# DM_V1_FPGA.net
KiCad netlist of a schematic drawn in Altium Designer
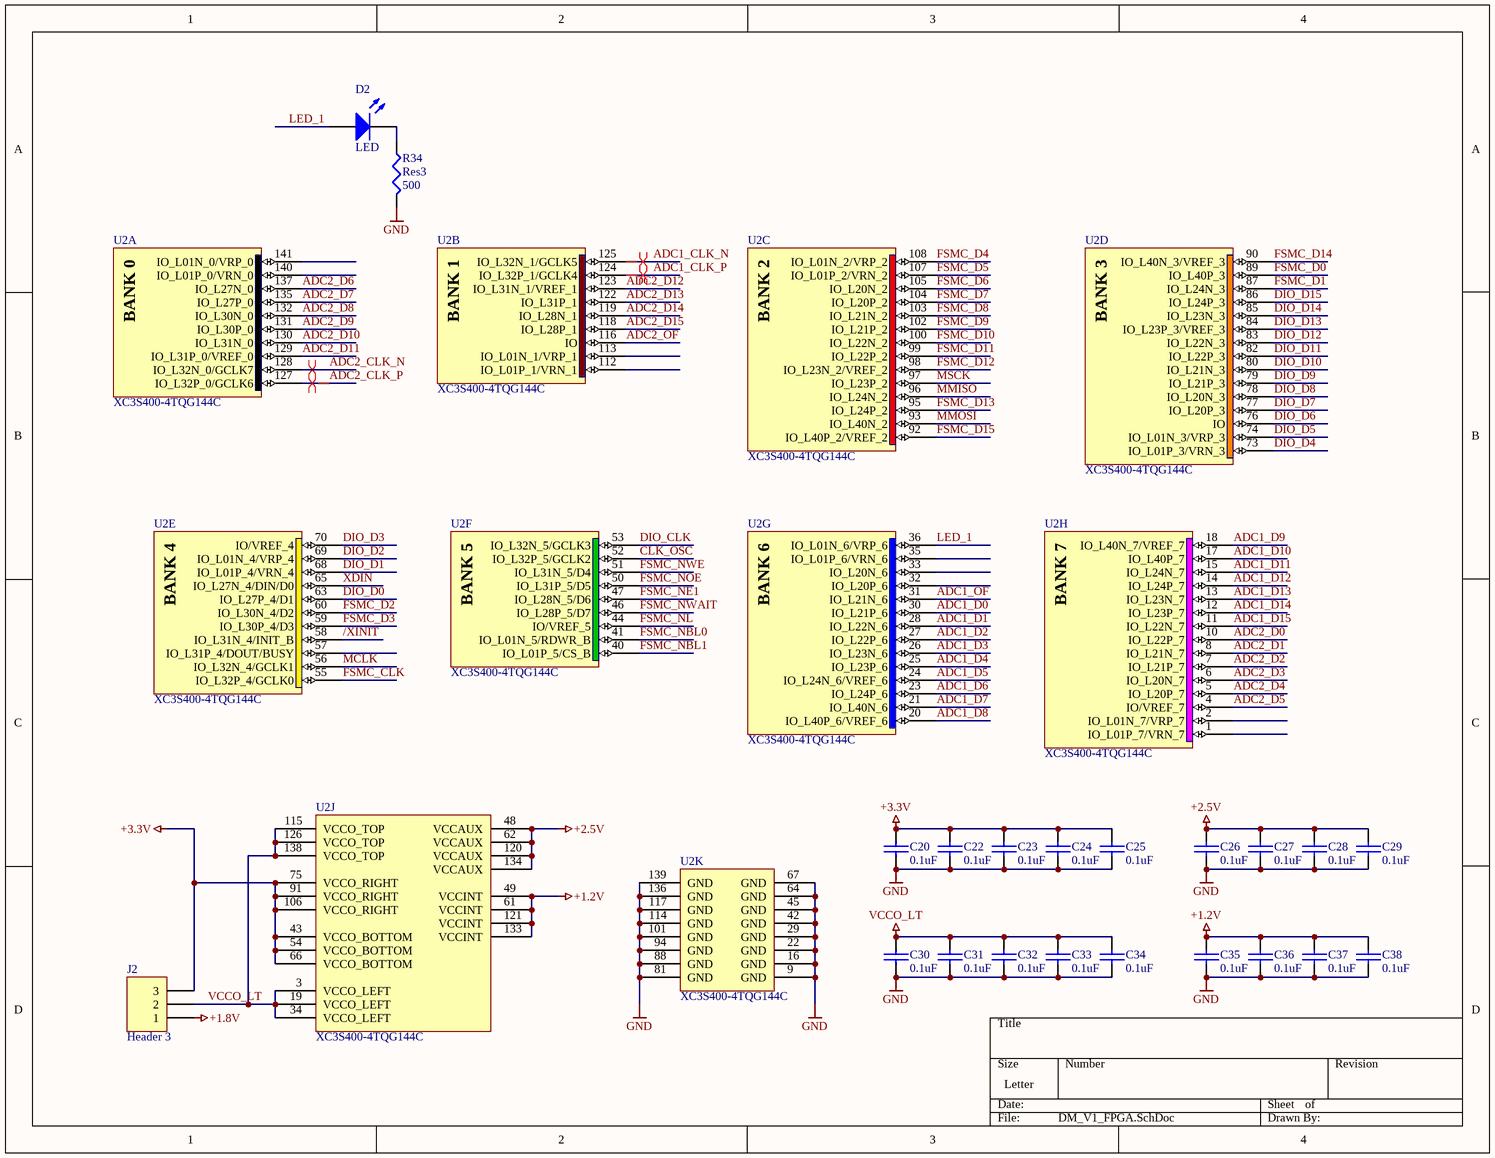
[diagram p0: DM_V1_FPGA.SchDoc]

(export (version "E")
  (design (tool "Eeschema 10.0.6"))
  (components
    (comp (ref "C20")
      (value "0.1uF")
      (footprint "1608[0603]")
      (description "Ceramic Chip-capacitor 0603")
      (fields (field (name "VOLTAGE") "25") (field (name "Comment") "0.1"))
      (libsource (lib "ISCapacitor") (part "CC0603-0.1MKF X7R"))
    )
    (comp (ref "C22")
      (value "0.1uF")
      (footprint "1608[0603]")
      (description "Ceramic Chip-capacitor 0603")
      (fields (field (name "VOLTAGE") "25") (field (name "Comment") "0.1"))
      (libsource (lib "ISCapacitor") (part "CC0603-0.1MKF X7R"))
    )
    (comp (ref "C23")
      (value "0.1uF")
      (footprint "1608[0603]")
      (description "Ceramic Chip-capacitor 0603")
      (fields (field (name "VOLTAGE") "25") (field (name "Comment") "0.1"))
      (libsource (lib "ISCapacitor") (part "CC0603-0.1MKF X7R"))
    )
    (comp (ref "C24")
      (value "0.1uF")
      (footprint "1608[0603]")
      (description "Ceramic Chip-capacitor 0603")
      (fields (field (name "VOLTAGE") "25") (field (name "Comment") "0.1"))
      (libsource (lib "ISCapacitor") (part "CC0603-0.1MKF X7R"))
    )
    (comp (ref "C25")
      (value "0.1uF")
      (footprint "1608[0603]")
      (description "Ceramic Chip-capacitor 0603")
      (fields (field (name "VOLTAGE") "25") (field (name "Comment") "0.1"))
      (libsource (lib "ISCapacitor") (part "CC0603-0.1MKF X7R"))
    )
    (comp (ref "C26")
      (value "0.1uF")
      (footprint "1608[0603]")
      (description "Ceramic Chip-capacitor 0603")
      (fields (field (name "VOLTAGE") "25") (field (name "Comment") "0.1"))
      (libsource (lib "ISCapacitor") (part "CC0603-0.1MKF X7R"))
    )
    (comp (ref "C27")
      (value "0.1uF")
      (footprint "1608[0603]")
      (description "Ceramic Chip-capacitor 0603")
      (fields (field (name "VOLTAGE") "25") (field (name "Comment") "0.1"))
      (libsource (lib "ISCapacitor") (part "CC0603-0.1MKF X7R"))
    )
    (comp (ref "C28")
      (value "0.1uF")
      (footprint "1608[0603]")
      (description "Ceramic Chip-capacitor 0603")
      (fields (field (name "VOLTAGE") "25") (field (name "Comment") "0.1"))
      (libsource (lib "ISCapacitor") (part "CC0603-0.1MKF X7R"))
    )
    (comp (ref "C29")
      (value "0.1uF")
      (footprint "1608[0603]")
      (description "Ceramic Chip-capacitor 0603")
      (fields (field (name "VOLTAGE") "25") (field (name "Comment") "0.1"))
      (libsource (lib "ISCapacitor") (part "CC0603-0.1MKF X7R"))
    )
    (comp (ref "C30")
      (value "0.1uF")
      (footprint "1608[0603]")
      (description "Ceramic Chip-capacitor 0603")
      (fields (field (name "VOLTAGE") "25") (field (name "Comment") "0.1"))
      (libsource (lib "ISCapacitor") (part "CC0603-0.1MKF X7R"))
    )
    (comp (ref "C31")
      (value "0.1uF")
      (footprint "1608[0603]")
      (description "Ceramic Chip-capacitor 0603")
      (fields (field (name "VOLTAGE") "25") (field (name "Comment") "0.1"))
      (libsource (lib "ISCapacitor") (part "CC0603-0.1MKF X7R"))
    )
    (comp (ref "C32")
      (value "0.1uF")
      (footprint "1608[0603]")
      (description "Ceramic Chip-capacitor 0603")
      (fields (field (name "VOLTAGE") "25") (field (name "Comment") "0.1"))
      (libsource (lib "ISCapacitor") (part "CC0603-0.1MKF X7R"))
    )
    (comp (ref "C33")
      (value "0.1uF")
      (footprint "1608[0603]")
      (description "Ceramic Chip-capacitor 0603")
      (fields (field (name "VOLTAGE") "25") (field (name "Comment") "0.1"))
      (libsource (lib "ISCapacitor") (part "CC0603-0.1MKF X7R"))
    )
    (comp (ref "C34")
      (value "0.1uF")
      (footprint "1608[0603]")
      (description "Ceramic Chip-capacitor 0603")
      (fields (field (name "VOLTAGE") "25") (field (name "Comment") "0.1"))
      (libsource (lib "ISCapacitor") (part "CC0603-0.1MKF X7R"))
    )
    (comp (ref "C35")
      (value "0.1uF")
      (footprint "1608[0603]")
      (description "Ceramic Chip-capacitor 0603")
      (fields (field (name "VOLTAGE") "25") (field (name "Comment") "0.1"))
      (libsource (lib "ISCapacitor") (part "CC0603-0.1MKF X7R"))
    )
    (comp (ref "C36")
      (value "0.1uF")
      (footprint "1608[0603]")
      (description "Ceramic Chip-capacitor 0603")
      (fields (field (name "VOLTAGE") "25") (field (name "Comment") "0.1"))
      (libsource (lib "ISCapacitor") (part "CC0603-0.1MKF X7R"))
    )
    (comp (ref "C37")
      (value "0.1uF")
      (footprint "1608[0603]")
      (description "Ceramic Chip-capacitor 0603")
      (fields (field (name "VOLTAGE") "25") (field (name "Comment") "0.1"))
      (libsource (lib "ISCapacitor") (part "CC0603-0.1MKF X7R"))
    )
    (comp (ref "C38")
      (value "0.1uF")
      (footprint "1608[0603]")
      (description "Ceramic Chip-capacitor 0603")
      (fields (field (name "VOLTAGE") "25") (field (name "Comment") "0.1"))
      (libsource (lib "ISCapacitor") (part "CC0603-0.1MKF X7R"))
    )
    (comp (ref "D2")
      (value "LED")
      (footprint "1608[0603]")
      (description "Typical RED, GREEN, YELLOW, AMBER GaAs LED")
      (fields (field (name "PUBLISHER") "Altium Limited"))
      (libsource (lib "Miscellaneous Devices") (part "LED2"))
    )
    (comp (ref "J2")
      (value "Header 3")
      (footprint "HDR1X3")
      (description "Header, 3-Pin")
      (fields (field (name "PUBLISHER") "Altium Limited"))
      (libsource (lib "Miscellaneous Connectors") (part "Header 3"))
    )
    (comp (ref "R34")
      (value "Res3")
      (footprint "J1-0603")
      (description "Resistor")
      (fields (field (name "ALTIUM_VALUE") "500") (field (name "PUBLISHER") "Altium Limited"))
      (libsource (lib "Miscellaneous Devices") (part "Res3"))
    )
    (comp (ref "U2")
      (value "XC3S400-4TQG144C")
      (footprint "TQG144_N")
      (description "Spartan-3 1.2V FPGA, 97 User I/Os, 144-Pin TQFP, Standard Performance, Commercial Grade, Pb-Free")
      (fields (field (name "PUBLISHER") "Altium Limited"))
      (libsource (lib "Xilinx Spartan-3") (part "XC3S400-4TQG144C"))
    )
  )
  (nets
    (net (code "1") (name "+1.2V") (class "Default")
      (node (ref "C35") (pin "2") (pintype "passive"))
      (node (ref "C36") (pin "2") (pintype "passive"))
      (node (ref "C37") (pin "2") (pintype "passive"))
      (node (ref "C38") (pin "2") (pintype "passive"))
      (node (ref "U2") (pin "121") (pinfunction "VCCINT_121") (pintype "power_in"))
      (node (ref "U2") (pin "133") (pinfunction "VCCINT_133") (pintype "power_in"))
      (node (ref "U2") (pin "49") (pinfunction "VCCINT_49") (pintype "power_in"))
      (node (ref "U2") (pin "61") (pinfunction "VCCINT_61") (pintype "power_in"))
    )
    (net (code "2") (name "+1.8V") (class "Default")
      (node (ref "J2") (pin "1") (pinfunction "1_1") (pintype "passive"))
    )
    (net (code "3") (name "+2.5V") (class "Default")
      (node (ref "C26") (pin "2") (pintype "passive"))
      (node (ref "C27") (pin "2") (pintype "passive"))
      (node (ref "C28") (pin "2") (pintype "passive"))
      (node (ref "C29") (pin "2") (pintype "passive"))
      (node (ref "U2") (pin "120") (pinfunction "VCCAUX_120") (pintype "power_in"))
      (node (ref "U2") (pin "134") (pinfunction "VCCAUX_134") (pintype "power_in"))
      (node (ref "U2") (pin "48") (pinfunction "VCCAUX_48") (pintype "power_in"))
      (node (ref "U2") (pin "62") (pinfunction "VCCAUX_62") (pintype "power_in"))
    )
    (net (code "4") (name "+3.3V") (class "Default")
      (node (ref "C20") (pin "2") (pintype "passive"))
      (node (ref "C22") (pin "2") (pintype "passive"))
      (node (ref "C23") (pin "2") (pintype "passive"))
      (node (ref "C24") (pin "2") (pintype "passive"))
      (node (ref "C25") (pin "2") (pintype "passive"))
      (node (ref "J2") (pin "3") (pinfunction "3_3") (pintype "passive"))
      (node (ref "U2") (pin "106") (pinfunction "VCCO_RIGHT_106") (pintype "power_in"))
      (node (ref "U2") (pin "43") (pinfunction "VCCO_BOTTOM_43") (pintype "power_in"))
      (node (ref "U2") (pin "54") (pinfunction "VCCO_BOTTOM_54") (pintype "power_in"))
      (node (ref "U2") (pin "66") (pinfunction "VCCO_BOTTOM_66") (pintype "power_in"))
      (node (ref "U2") (pin "75") (pinfunction "VCCO_RIGHT_75") (pintype "power_in"))
      (node (ref "U2") (pin "91") (pinfunction "VCCO_RIGHT_91") (pintype "power_in"))
    )
    (net (code "5") (name "/ADC1_CLK_N") (class "Default")
      (node (ref "U2") (pin "125") (pinfunction "IO_L32N_1/GCLK5_125") (pintype "bidirectional"))
    )
    (net (code "6") (name "/ADC1_CLK_P") (class "Default")
      (node (ref "U2") (pin "124") (pinfunction "IO_L32P_1/GCLK4_124") (pintype "bidirectional"))
    )
    (net (code "7") (name "/ADC1_D0") (class "Default")
      (node (ref "U2") (pin "30") (pinfunction "IO_L21P_6_30") (pintype "bidirectional"))
    )
    (net (code "8") (name "/ADC1_D1") (class "Default")
      (node (ref "U2") (pin "28") (pinfunction "IO_L22N_6_28") (pintype "bidirectional"))
    )
    (net (code "9") (name "/ADC1_D2") (class "Default")
      (node (ref "U2") (pin "27") (pinfunction "IO_L22P_6_27") (pintype "bidirectional"))
    )
    (net (code "10") (name "/ADC1_D3") (class "Default")
      (node (ref "U2") (pin "26") (pinfunction "IO_L23N_6_26") (pintype "bidirectional"))
    )
    (net (code "11") (name "/ADC1_D4") (class "Default")
      (node (ref "U2") (pin "25") (pinfunction "IO_L23P_6_25") (pintype "bidirectional"))
    )
    (net (code "12") (name "/ADC1_D5") (class "Default")
      (node (ref "U2") (pin "24") (pinfunction "IO_L24N_6/VREF_6_24") (pintype "bidirectional"))
    )
    (net (code "13") (name "/ADC1_D6") (class "Default")
      (node (ref "U2") (pin "23") (pinfunction "IO_L24P_6_23") (pintype "bidirectional"))
    )
    (net (code "14") (name "/ADC1_D7") (class "Default")
      (node (ref "U2") (pin "21") (pinfunction "IO_L40N_6_21") (pintype "bidirectional"))
    )
    (net (code "15") (name "/ADC1_D8") (class "Default")
      (node (ref "U2") (pin "20") (pinfunction "IO_L40P_6/VREF_6_20") (pintype "bidirectional"))
    )
    (net (code "16") (name "/ADC1_D9") (class "Default")
      (node (ref "U2") (pin "18") (pinfunction "IO_L40N_7/VREF_7_18") (pintype "bidirectional"))
    )
    (net (code "17") (name "/ADC1_D10") (class "Default")
      (node (ref "U2") (pin "17") (pinfunction "IO_L40P_7_17") (pintype "bidirectional"))
    )
    (net (code "18") (name "/ADC1_D11") (class "Default")
      (node (ref "U2") (pin "15") (pinfunction "IO_L24N_7_15") (pintype "bidirectional"))
    )
    (net (code "19") (name "/ADC1_D12") (class "Default")
      (node (ref "U2") (pin "14") (pinfunction "IO_L24P_7_14") (pintype "bidirectional"))
    )
    (net (code "20") (name "/ADC1_D13") (class "Default")
      (node (ref "U2") (pin "13") (pinfunction "IO_L23N_7_13") (pintype "bidirectional"))
    )
    (net (code "21") (name "/ADC1_D14") (class "Default")
      (node (ref "U2") (pin "12") (pinfunction "IO_L23P_7_12") (pintype "bidirectional"))
    )
    (net (code "22") (name "/ADC1_D15") (class "Default")
      (node (ref "U2") (pin "11") (pinfunction "IO_L22N_7_11") (pintype "bidirectional"))
    )
    (net (code "23") (name "/ADC1_OF") (class "Default")
      (node (ref "U2") (pin "31") (pinfunction "IO_L21N_6_31") (pintype "bidirectional"))
    )
    (net (code "24") (name "/ADC2_CLK_N") (class "Default")
      (node (ref "U2") (pin "128") (pinfunction "IO_L32N_0/GCLK7_128") (pintype "bidirectional"))
    )
    (net (code "25") (name "/ADC2_CLK_P") (class "Default")
      (node (ref "U2") (pin "127") (pinfunction "IO_L32P_0/GCLK6_127") (pintype "bidirectional"))
    )
    (net (code "26") (name "/ADC2_D0") (class "Default")
      (node (ref "U2") (pin "10") (pinfunction "IO_L22P_7_10") (pintype "bidirectional"))
    )
    (net (code "27") (name "/ADC2_D1") (class "Default")
      (node (ref "U2") (pin "8") (pinfunction "IO_L21N_7_8") (pintype "bidirectional"))
    )
    (net (code "28") (name "/ADC2_D2") (class "Default")
      (node (ref "U2") (pin "7") (pinfunction "IO_L21P_7_7") (pintype "bidirectional"))
    )
    (net (code "29") (name "/ADC2_D3") (class "Default")
      (node (ref "U2") (pin "6") (pinfunction "IO_L20N_7_6") (pintype "bidirectional"))
    )
    (net (code "30") (name "/ADC2_D4") (class "Default")
      (node (ref "U2") (pin "5") (pinfunction "IO_L20P_7_5") (pintype "bidirectional"))
    )
    (net (code "31") (name "/ADC2_D5") (class "Default")
      (node (ref "U2") (pin "4") (pinfunction "IO/VREF_7_4") (pintype "bidirectional"))
    )
    (net (code "32") (name "/ADC2_D6") (class "Default")
      (node (ref "U2") (pin "137") (pinfunction "IO_L27N_0_137") (pintype "bidirectional"))
    )
    (net (code "33") (name "/ADC2_D7") (class "Default")
      (node (ref "U2") (pin "135") (pinfunction "IO_L27P_0_135") (pintype "bidirectional"))
    )
    (net (code "34") (name "/ADC2_D8") (class "Default")
      (node (ref "U2") (pin "132") (pinfunction "IO_L30N_0_132") (pintype "bidirectional"))
    )
    (net (code "35") (name "/ADC2_D9") (class "Default")
      (node (ref "U2") (pin "131") (pinfunction "IO_L30P_0_131") (pintype "bidirectional"))
    )
    (net (code "36") (name "/ADC2_D10") (class "Default")
      (node (ref "U2") (pin "130") (pinfunction "IO_L31N_0_130") (pintype "bidirectional"))
    )
    (net (code "37") (name "/ADC2_D11") (class "Default")
      (node (ref "U2") (pin "129") (pinfunction "IO_L31P_0/VREF_0_129") (pintype "bidirectional"))
    )
    (net (code "38") (name "/ADC2_D12") (class "Default")
      (node (ref "U2") (pin "123") (pinfunction "IO_L31N_1/VREF_1_123") (pintype "bidirectional"))
    )
    (net (code "39") (name "/ADC2_D13") (class "Default")
      (node (ref "U2") (pin "122") (pinfunction "IO_L31P_1_122") (pintype "bidirectional"))
    )
    (net (code "40") (name "/ADC2_D14") (class "Default")
      (node (ref "U2") (pin "119") (pinfunction "IO_L28N_1_119") (pintype "bidirectional"))
    )
    (net (code "41") (name "/ADC2_D15") (class "Default")
      (node (ref "U2") (pin "118") (pinfunction "IO_L28P_1_118") (pintype "bidirectional"))
    )
    (net (code "42") (name "/ADC2_OF") (class "Default")
      (node (ref "U2") (pin "116") (pinfunction "IO_116") (pintype "bidirectional"))
    )
    (net (code "43") (name "/CLK_OSC") (class "Default")
      (node (ref "U2") (pin "52") (pinfunction "IO_L32P_5/GCLK2_52") (pintype "bidirectional"))
    )
    (net (code "44") (name "/DIO_CLK") (class "Default")
      (node (ref "U2") (pin "53") (pinfunction "IO_L32N_5/GCLK3_53") (pintype "bidirectional"))
    )
    (net (code "45") (name "/DIO_D0") (class "Default")
      (node (ref "U2") (pin "63") (pinfunction "IO_L27P_4/D1_63") (pintype "bidirectional"))
    )
    (net (code "46") (name "/DIO_D1") (class "Default")
      (node (ref "U2") (pin "68") (pinfunction "IO_L01P_4/VRN_4_68") (pintype "bidirectional"))
    )
    (net (code "47") (name "/DIO_D2") (class "Default")
      (node (ref "U2") (pin "69") (pinfunction "IO_L01N_4/VRP_4_69") (pintype "bidirectional"))
    )
    (net (code "48") (name "/DIO_D3") (class "Default")
      (node (ref "U2") (pin "70") (pinfunction "IO/VREF_4_70") (pintype "bidirectional"))
    )
    (net (code "49") (name "/DIO_D4") (class "Default")
      (node (ref "U2") (pin "73") (pinfunction "IO_L01P_3/VRN_3_73") (pintype "bidirectional"))
    )
    (net (code "50") (name "/DIO_D5") (class "Default")
      (node (ref "U2") (pin "74") (pinfunction "IO_L01N_3/VRP_3_74") (pintype "bidirectional"))
    )
    (net (code "51") (name "/DIO_D6") (class "Default")
      (node (ref "U2") (pin "76") (pinfunction "IO_76") (pintype "bidirectional"))
    )
    (net (code "52") (name "/DIO_D7") (class "Default")
      (node (ref "U2") (pin "77") (pinfunction "IO_L20P_3_77") (pintype "bidirectional"))
    )
    (net (code "53") (name "/DIO_D8") (class "Default")
      (node (ref "U2") (pin "78") (pinfunction "IO_L20N_3_78") (pintype "bidirectional"))
    )
    (net (code "54") (name "/DIO_D9") (class "Default")
      (node (ref "U2") (pin "79") (pinfunction "IO_L21P_3_79") (pintype "bidirectional"))
    )
    (net (code "55") (name "/DIO_D10") (class "Default")
      (node (ref "U2") (pin "80") (pinfunction "IO_L21N_3_80") (pintype "bidirectional"))
    )
    (net (code "56") (name "/DIO_D11") (class "Default")
      (node (ref "U2") (pin "82") (pinfunction "IO_L22P_3_82") (pintype "bidirectional"))
    )
    (net (code "57") (name "/DIO_D12") (class "Default")
      (node (ref "U2") (pin "83") (pinfunction "IO_L22N_3_83") (pintype "bidirectional"))
    )
    (net (code "58") (name "/DIO_D13") (class "Default")
      (node (ref "U2") (pin "84") (pinfunction "IO_L23P_3/VREF_3_84") (pintype "bidirectional"))
    )
    (net (code "59") (name "/DIO_D14") (class "Default")
      (node (ref "U2") (pin "85") (pinfunction "IO_L23N_3_85") (pintype "bidirectional"))
    )
    (net (code "60") (name "/DIO_D15") (class "Default")
      (node (ref "U2") (pin "86") (pinfunction "IO_L24P_3_86") (pintype "bidirectional"))
    )
    (net (code "61") (name "/FSMC_CLK") (class "Default")
      (node (ref "U2") (pin "55") (pinfunction "IO_L32P_4/GCLK0_55") (pintype "bidirectional"))
    )
    (net (code "62") (name "/FSMC_D0") (class "Default")
      (node (ref "U2") (pin "89") (pinfunction "IO_L40P_3_89") (pintype "bidirectional"))
    )
    (net (code "63") (name "/FSMC_D1") (class "Default")
      (node (ref "U2") (pin "87") (pinfunction "IO_L24N_3_87") (pintype "bidirectional"))
    )
    (net (code "64") (name "/FSMC_D2") (class "Default")
      (node (ref "U2") (pin "60") (pinfunction "IO_L30N_4/D2_60") (pintype "bidirectional"))
    )
    (net (code "65") (name "/FSMC_D3") (class "Default")
      (node (ref "U2") (pin "59") (pinfunction "IO_L30P_4/D3_59") (pintype "bidirectional"))
    )
    (net (code "66") (name "/FSMC_D4") (class "Default")
      (node (ref "U2") (pin "108") (pinfunction "IO_L01N_2/VRP_2_108") (pintype "bidirectional"))
    )
    (net (code "67") (name "/FSMC_D5") (class "Default")
      (node (ref "U2") (pin "107") (pinfunction "IO_L01P_2/VRN_2_107") (pintype "bidirectional"))
    )
    (net (code "68") (name "/FSMC_D6") (class "Default")
      (node (ref "U2") (pin "105") (pinfunction "IO_L20N_2_105") (pintype "bidirectional"))
    )
    (net (code "69") (name "/FSMC_D7") (class "Default")
      (node (ref "U2") (pin "104") (pinfunction "IO_L20P_2_104") (pintype "bidirectional"))
    )
    (net (code "70") (name "/FSMC_D8") (class "Default")
      (node (ref "U2") (pin "103") (pinfunction "IO_L21N_2_103") (pintype "bidirectional"))
    )
    (net (code "71") (name "/FSMC_D9") (class "Default")
      (node (ref "U2") (pin "102") (pinfunction "IO_L21P_2_102") (pintype "bidirectional"))
    )
    (net (code "72") (name "/FSMC_D10") (class "Default")
      (node (ref "U2") (pin "100") (pinfunction "IO_L22N_2_100") (pintype "bidirectional"))
    )
    (net (code "73") (name "/FSMC_D11") (class "Default")
      (node (ref "U2") (pin "99") (pinfunction "IO_L22P_2_99") (pintype "bidirectional"))
    )
    (net (code "74") (name "/FSMC_D12") (class "Default")
      (node (ref "U2") (pin "98") (pinfunction "IO_L23N_2/VREF_2_98") (pintype "bidirectional"))
    )
    (net (code "75") (name "/FSMC_D13") (class "Default")
      (node (ref "U2") (pin "95") (pinfunction "IO_L24P_2_95") (pintype "bidirectional"))
    )
    (net (code "76") (name "/FSMC_D14") (class "Default")
      (node (ref "U2") (pin "90") (pinfunction "IO_L40N_3/VREF_3_90") (pintype "bidirectional"))
    )
    (net (code "77") (name "/FSMC_D15") (class "Default")
      (node (ref "U2") (pin "92") (pinfunction "IO_L40P_2/VREF_2_92") (pintype "bidirectional"))
    )
    (net (code "78") (name "/FSMC_NBL0") (class "Default")
      (node (ref "U2") (pin "41") (pinfunction "IO_L01N_5/RDWR_B_41") (pintype "bidirectional"))
    )
    (net (code "79") (name "/FSMC_NBL1") (class "Default")
      (node (ref "U2") (pin "40") (pinfunction "IO_L01P_5/CS_B_40") (pintype "bidirectional"))
    )
    (net (code "80") (name "/FSMC_NE1") (class "Default")
      (node (ref "U2") (pin "47") (pinfunction "IO_L28N_5/D6_47") (pintype "bidirectional"))
    )
    (net (code "81") (name "/FSMC_NL") (class "Default")
      (node (ref "U2") (pin "44") (pinfunction "IO/VREF_5_44") (pintype "bidirectional"))
    )
    (net (code "82") (name "/FSMC_NOE") (class "Default")
      (node (ref "U2") (pin "50") (pinfunction "IO_L31P_5/D5_50") (pintype "bidirectional"))
    )
    (net (code "83") (name "/FSMC_NWAIT") (class "Default")
      (node (ref "U2") (pin "46") (pinfunction "IO_L28P_5/D7_46") (pintype "bidirectional"))
    )
    (net (code "84") (name "/FSMC_NWE") (class "Default")
      (node (ref "U2") (pin "51") (pinfunction "IO_L31N_5/D4_51") (pintype "bidirectional"))
    )
    (net (code "85") (name "/LED_1") (class "Default")
      (node (ref "D2") (pin "1") (pinfunction "A_1") (pintype "passive"))
      (node (ref "U2") (pin "36") (pinfunction "IO_L01N_6/VRP_6_36") (pintype "bidirectional"))
    )
    (net (code "86") (name "/MCLK") (class "Default")
      (node (ref "U2") (pin "56") (pinfunction "IO_L32N_4/GCLK1_56") (pintype "bidirectional"))
    )
    (net (code "87") (name "/MMISO") (class "Default")
      (node (ref "U2") (pin "96") (pinfunction "IO_L24N_2_96") (pintype "bidirectional"))
    )
    (net (code "88") (name "/MMOSI") (class "Default")
      (node (ref "U2") (pin "93") (pinfunction "IO_L40N_2_93") (pintype "bidirectional"))
    )
    (net (code "89") (name "/MSCK") (class "Default")
      (node (ref "U2") (pin "97") (pinfunction "IO_L23P_2_97") (pintype "bidirectional"))
    )
    (net (code "90") (name "/XDIN") (class "Default")
      (node (ref "U2") (pin "65") (pinfunction "IO_L27N_4/DIN/D0_65") (pintype "bidirectional"))
    )
    (net (code "91") (name "/{slash}XINIT") (class "Default")
      (node (ref "U2") (pin "58") (pinfunction "IO_L31N_4/INIT_B_58") (pintype "bidirectional"))
    )
    (net (code "92") (name "GND") (class "Default")
      (node (ref "C20") (pin "1") (pintype "passive"))
      (node (ref "C22") (pin "1") (pintype "passive"))
      (node (ref "C23") (pin "1") (pintype "passive"))
      (node (ref "C24") (pin "1") (pintype "passive"))
      (node (ref "C25") (pin "1") (pintype "passive"))
      (node (ref "C26") (pin "1") (pintype "passive"))
      (node (ref "C27") (pin "1") (pintype "passive"))
      (node (ref "C28") (pin "1") (pintype "passive"))
      (node (ref "C29") (pin "1") (pintype "passive"))
      (node (ref "C30") (pin "1") (pintype "passive"))
      (node (ref "C31") (pin "1") (pintype "passive"))
      (node (ref "C32") (pin "1") (pintype "passive"))
      (node (ref "C33") (pin "1") (pintype "passive"))
      (node (ref "C34") (pin "1") (pintype "passive"))
      (node (ref "C35") (pin "1") (pintype "passive"))
      (node (ref "C36") (pin "1") (pintype "passive"))
      (node (ref "C37") (pin "1") (pintype "passive"))
      (node (ref "C38") (pin "1") (pintype "passive"))
      (node (ref "R34") (pin "2") (pinfunction "2_2") (pintype "passive"))
      (node (ref "U2") (pin "101") (pinfunction "GND_101") (pintype "power_in"))
      (node (ref "U2") (pin "114") (pinfunction "GND_114") (pintype "power_in"))
      (node (ref "U2") (pin "117") (pinfunction "GND_117") (pintype "power_in"))
      (node (ref "U2") (pin "136") (pinfunction "GND_136") (pintype "power_in"))
      (node (ref "U2") (pin "139") (pinfunction "GND_139") (pintype "power_in"))
      (node (ref "U2") (pin "16") (pinfunction "GND_16") (pintype "power_in"))
      (node (ref "U2") (pin "22") (pinfunction "GND_22") (pintype "power_in"))
      (node (ref "U2") (pin "29") (pinfunction "GND_29") (pintype "power_in"))
      (node (ref "U2") (pin "42") (pinfunction "GND_42") (pintype "power_in"))
      (node (ref "U2") (pin "45") (pinfunction "GND_45") (pintype "power_in"))
      (node (ref "U2") (pin "64") (pinfunction "GND_64") (pintype "power_in"))
      (node (ref "U2") (pin "67") (pinfunction "GND_67") (pintype "power_in"))
      (node (ref "U2") (pin "81") (pinfunction "GND_81") (pintype "power_in"))
      (node (ref "U2") (pin "88") (pinfunction "GND_88") (pintype "power_in"))
      (node (ref "U2") (pin "9") (pinfunction "GND_9") (pintype "power_in"))
      (node (ref "U2") (pin "94") (pinfunction "GND_94") (pintype "power_in"))
    )
    (net (code "93") (name "Net-(D2-K)") (class "Default")
      (node (ref "D2") (pin "2") (pinfunction "K_2") (pintype "passive"))
      (node (ref "R34") (pin "1") (pinfunction "1_1") (pintype "passive"))
    )
    (net (code "94") (name "VCCO_LT") (class "Default")
      (node (ref "C30") (pin "2") (pintype "passive"))
      (node (ref "C31") (pin "2") (pintype "passive"))
      (node (ref "C32") (pin "2") (pintype "passive"))
      (node (ref "C33") (pin "2") (pintype "passive"))
      (node (ref "C34") (pin "2") (pintype "passive"))
      (node (ref "J2") (pin "2") (pinfunction "2_2") (pintype "passive"))
      (node (ref "U2") (pin "115") (pinfunction "VCCO_TOP_115") (pintype "power_in"))
      (node (ref "U2") (pin "126") (pinfunction "VCCO_TOP_126") (pintype "power_in"))
      (node (ref "U2") (pin "138") (pinfunction "VCCO_TOP_138") (pintype "power_in"))
      (node (ref "U2") (pin "19") (pinfunction "VCCO_LEFT_19") (pintype "power_in"))
      (node (ref "U2") (pin "3") (pinfunction "VCCO_LEFT_3") (pintype "power_in"))
      (node (ref "U2") (pin "34") (pinfunction "VCCO_LEFT_34") (pintype "power_in"))
    )
    (net (code "95") (name "unconnected-(U2A-IO_L01N_0{slash}VRP_0-Pad141)") (class "Default")
      (node (ref "U2") (pin "141") (pinfunction "IO_L01N_0/VRP_0_141") (pintype "bidirectional"))
    )
    (net (code "96") (name "unconnected-(U2A-IO_L01P_0{slash}VRN_0-Pad140)") (class "Default")
      (node (ref "U2") (pin "140") (pinfunction "IO_L01P_0/VRN_0_140") (pintype "bidirectional"))
    )
    (net (code "97") (name "unconnected-(U2B-IO_L01N_1{slash}VRP_1-Pad113)") (class "Default")
      (node (ref "U2") (pin "113") (pinfunction "IO_L01N_1/VRP_1_113") (pintype "bidirectional"))
    )
    (net (code "98") (name "unconnected-(U2B-IO_L01P_1{slash}VRN_1-Pad112)") (class "Default")
      (node (ref "U2") (pin "112") (pinfunction "IO_L01P_1/VRN_1_112") (pintype "bidirectional"))
    )
    (net (code "99") (name "unconnected-(U2E-IO_L31P_4{slash}DOUT{slash}BUSY-Pad57)") (class "Default")
      (node (ref "U2") (pin "57") (pinfunction "IO_L31P_4/DOUT/BUSY_57") (pintype "bidirectional"))
    )
    (net (code "100") (name "unconnected-(U2G-IO_L01P_6{slash}VRN_6-Pad35)") (class "Default")
      (node (ref "U2") (pin "35") (pinfunction "IO_L01P_6/VRN_6_35") (pintype "bidirectional"))
    )
    (net (code "101") (name "unconnected-(U2G-IO_L20N_6-Pad33)") (class "Default")
      (node (ref "U2") (pin "33") (pinfunction "IO_L20N_6_33") (pintype "bidirectional"))
    )
    (net (code "102") (name "unconnected-(U2G-IO_L20P_6-Pad32)") (class "Default")
      (node (ref "U2") (pin "32") (pinfunction "IO_L20P_6_32") (pintype "bidirectional"))
    )
    (net (code "103") (name "unconnected-(U2H-IO_L01N_7{slash}VRP_7-Pad2)") (class "Default")
      (node (ref "U2") (pin "2") (pinfunction "IO_L01N_7/VRP_7_2") (pintype "bidirectional"))
    )
    (net (code "104") (name "unconnected-(U2H-IO_L01P_7{slash}VRN_7-Pad1)") (class "Default")
      (node (ref "U2") (pin "1") (pinfunction "IO_L01P_7/VRN_7_1") (pintype "bidirectional"))
    )
  )
)
